# Pedal_Board_-_ADC.net
KiCad netlist of a schematic drawn in Altium Designer
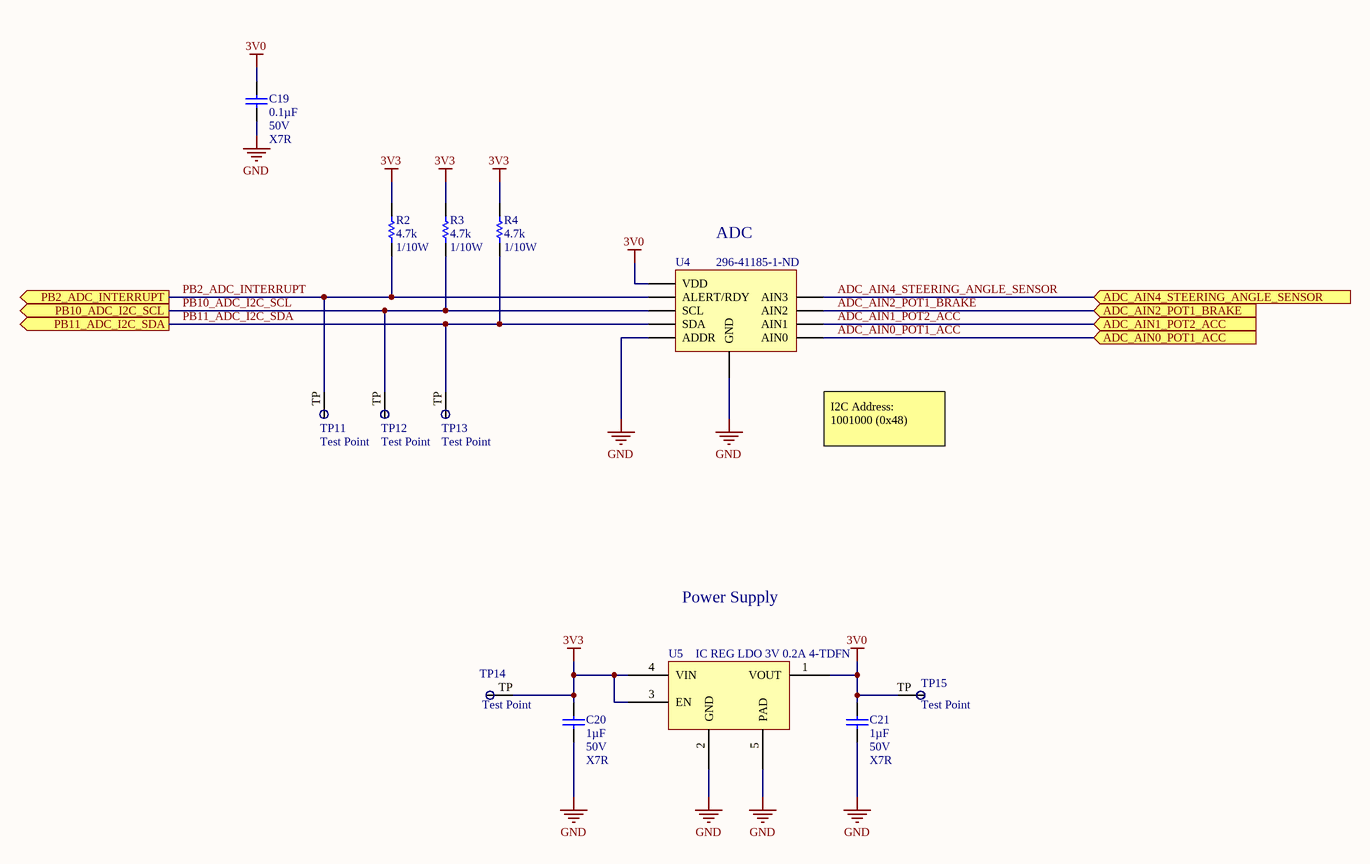
[diagram p0: Pedal Board - ADC.SchDoc]

(export (version "E")
  (design (tool "Eeschema 10.0.6"))
  (components
    (comp (ref "C19")
      (value "CAP CER 0.1UF 50V 10% X7R 0603")
      (footprint "CAP, 0603")
      (description "0.10µF ±10% 50V Ceramic Capacitor X7R 0603 (1608 Metric)")
      (fields
        (field (name "TOLERANCE") "±10%")
        (field (name "CAPACITANCE") "0.1µF")
        (field (name "VOLTAGE") "50V")
        (field (name "TEMPERATURE COEFFICIENT") "X7R")
      )
      (libsource (lib "Schematic Diagrams") (part "CAP CER 0.1UF 50V 10% X7R 0603"))
    )
    (comp (ref "C20")
      (value "CAP CER 1UF 50V 10% X7R 0603")
      (footprint "CAP, 0603")
      (description "1µF ±10% 50V Ceramic Capacitor X7R 0603 (1608 Metric)")
      (fields
        (field (name "TOLERANCE") "±10%")
        (field (name "CAPACITANCE") "1µF")
        (field (name "VOLTAGE") "50V")
        (field (name "TEMPERATURE COEFFICIENT") "X7R")
      )
      (libsource (lib "Schematic Diagrams") (part "CAP CER 1UF 50V 10% X7R 0603"))
    )
    (comp (ref "C21")
      (value "CAP CER 1UF 50V 10% X7R 0603")
      (footprint "CAP, 0603")
      (description "1µF ±10% 50V Ceramic Capacitor X7R 0603 (1608 Metric)")
      (fields
        (field (name "TOLERANCE") "±10%")
        (field (name "CAPACITANCE") "1µF")
        (field (name "VOLTAGE") "50V")
        (field (name "TEMPERATURE COEFFICIENT") "X7R")
      )
      (libsource (lib "Schematic Diagrams") (part "CAP CER 1UF 50V 10% X7R 0603"))
    )
    (comp (ref "R2")
      (value "RES 4.7K OHM 1% 1/10W 0603")
      (footprint "RES, 0603")
      (description "4.7k Ohm ±1% 0.1W, 1/10W Chip Resistor 0603 (1608 Metric) Moisture Resistant Thick Film")
      (fields
        (field (name "TOLERANCE") "±1%")
        (field (name "RESISTANCE (OHMS)") "4.7k")
        (field (name "POWER (WATTS)") "1/10W")
      )
      (libsource (lib "Schematic Diagrams") (part "RES 4.7K OHM 1% 1/10W 0603"))
    )
    (comp (ref "R3")
      (value "RES 4.7K OHM 1% 1/10W 0603")
      (footprint "RES, 0603")
      (description "4.7k Ohm ±1% 0.1W, 1/10W Chip Resistor 0603 (1608 Metric) Moisture Resistant Thick Film")
      (fields
        (field (name "TOLERANCE") "±1%")
        (field (name "RESISTANCE (OHMS)") "4.7k")
        (field (name "POWER (WATTS)") "1/10W")
      )
      (libsource (lib "Schematic Diagrams") (part "RES 4.7K OHM 1% 1/10W 0603"))
    )
    (comp (ref "R4")
      (value "RES 4.7K OHM 1% 1/10W 0603")
      (footprint "RES, 0603")
      (description "4.7k Ohm ±1% 0.1W, 1/10W Chip Resistor 0603 (1608 Metric) Moisture Resistant Thick Film")
      (fields
        (field (name "TOLERANCE") "±1%")
        (field (name "RESISTANCE (OHMS)") "4.7k")
        (field (name "POWER (WATTS)") "1/10W")
      )
      (libsource (lib "Schematic Diagrams") (part "RES 4.7K OHM 1% 1/10W 0603"))
    )
    (comp (ref "TP11")
      (value "Test Point")
      (footprint "Test Point")
      (libsource (lib "Schematic Diagrams") (part "Test Point"))
    )
    (comp (ref "TP12")
      (value "Test Point")
      (footprint "Test Point")
      (libsource (lib "Schematic Diagrams") (part "Test Point"))
    )
    (comp (ref "TP13")
      (value "Test Point")
      (footprint "Test Point")
      (libsource (lib "Schematic Diagrams") (part "Test Point"))
    )
    (comp (ref "TP14")
      (value "Test Point")
      (footprint "Test Point")
      (libsource (lib "Schematic Diagrams") (part "Test Point"))
    )
    (comp (ref "TP15")
      (value "Test Point")
      (footprint "Test Point")
      (libsource (lib "Schematic Diagrams") (part "Test Point"))
    )
    (comp (ref "U4")
      (value "Quad ADC")
      (footprint "IC ADC VSSOP10")
      (description "12 Bit Analog to Digital Converter 4 Input 1 Sigma-Delta 10-VSSOP")
      (fields
        (field (name "MANUFACTURER") "Texas Instruments")
        (field (name "MANUFACTURER PART NUMBER") "ADS1015IDGSR")
        (field (name "SUPPLIER PART NUMBER 1") "296-41185-1-ND")
      )
      (libsource (lib "Schematic Diagrams") (part "IC ADC 12-BIT VSSOP-10"))
    )
    (comp (ref "U5")
      (value "IC REG LDO 3V 0.2A 4-TDFN")
      (footprint "IC REG LDO 3V 0.2A 4-TDFN")
      (fields
        (field (name "MANUFACTURER") "Microchip Technology")
        (field (name "MANUFACTURER PART NUMBER") "MIC94310-PYMT-TR")
      )
      (libsource (lib "Schematic Diagrams") (part "IC REG LDO 3V 0.2A 4-TDFN"))
    )
  )
  (nets
    (net (code "1") (name "/ADC_AIN0_POT1_ACC") (class "Default")
      (node (ref "U4") (pin "4") (pinfunction "AIN0_4") (pintype "passive"))
    )
    (net (code "2") (name "/ADC_AIN1_POT2_ACC") (class "Default")
      (node (ref "U4") (pin "5") (pinfunction "AIN1_5") (pintype "passive"))
    )
    (net (code "3") (name "/ADC_AIN2_POT1_BRAKE") (class "Default")
      (node (ref "U4") (pin "6") (pinfunction "AIN2_6") (pintype "passive"))
    )
    (net (code "4") (name "/ADC_AIN4_STEERING_ANGLE_SENSOR") (class "Default")
      (node (ref "U4") (pin "7") (pinfunction "AIN3_7") (pintype "passive"))
    )
    (net (code "5") (name "/PB2_ADC_INTERRUPT") (class "Default")
      (node (ref "R2") (pin "2") (pinfunction "2_2") (pintype "passive"))
      (node (ref "TP11") (pin "TP") (pinfunction "1_TP") (pintype "passive"))
      (node (ref "U4") (pin "2") (pinfunction "ALERT/RDY_2") (pintype "passive"))
    )
    (net (code "6") (name "/PB10_ADC_I2C_SCL") (class "Default")
      (node (ref "R3") (pin "2") (pinfunction "2_2") (pintype "passive"))
      (node (ref "TP12") (pin "TP") (pinfunction "1_TP") (pintype "passive"))
      (node (ref "U4") (pin "10") (pinfunction "SCL_10") (pintype "passive"))
    )
    (net (code "7") (name "/PB11_ADC_I2C_SDA") (class "Default")
      (node (ref "R4") (pin "2") (pinfunction "2_2") (pintype "passive"))
      (node (ref "TP13") (pin "TP") (pinfunction "1_TP") (pintype "passive"))
      (node (ref "U4") (pin "9") (pinfunction "SDA_9") (pintype "passive"))
    )
    (net (code "8") (name "3V0") (class "Default")
      (node (ref "C19") (pin "1") (pinfunction "1_1") (pintype "passive"))
      (node (ref "C21") (pin "1") (pinfunction "1_1") (pintype "passive"))
      (node (ref "TP15") (pin "TP") (pinfunction "1_TP") (pintype "passive"))
      (node (ref "U4") (pin "8") (pinfunction "VDD_8") (pintype "passive"))
      (node (ref "U5") (pin "1") (pinfunction "VOUT_1") (pintype "passive"))
    )
    (net (code "9") (name "3V3") (class "Default")
      (node (ref "C20") (pin "1") (pinfunction "1_1") (pintype "passive"))
      (node (ref "R2") (pin "1") (pinfunction "1_1") (pintype "passive"))
      (node (ref "R3") (pin "1") (pinfunction "1_1") (pintype "passive"))
      (node (ref "R4") (pin "1") (pinfunction "1_1") (pintype "passive"))
      (node (ref "TP14") (pin "TP") (pinfunction "1_TP") (pintype "passive"))
      (node (ref "U5") (pin "3") (pinfunction "EN_3") (pintype "passive"))
      (node (ref "U5") (pin "4") (pinfunction "VIN_4") (pintype "passive"))
    )
    (net (code "10") (name "GND") (class "Default")
      (node (ref "C19") (pin "2") (pinfunction "2_2") (pintype "passive"))
      (node (ref "C20") (pin "2") (pinfunction "2_2") (pintype "passive"))
      (node (ref "C21") (pin "2") (pinfunction "2_2") (pintype "passive"))
      (node (ref "U4") (pin "1") (pinfunction "ADDR_1") (pintype "passive"))
      (node (ref "U4") (pin "3") (pinfunction "GND_3") (pintype "passive"))
      (node (ref "U5") (pin "2") (pinfunction "GND_2") (pintype "passive"))
      (node (ref "U5") (pin "5") (pinfunction "PAD_5") (pintype "passive"))
    )
  )
)
